# CORESP12.net
KiCad netlist of a schematic drawn in EAGLE
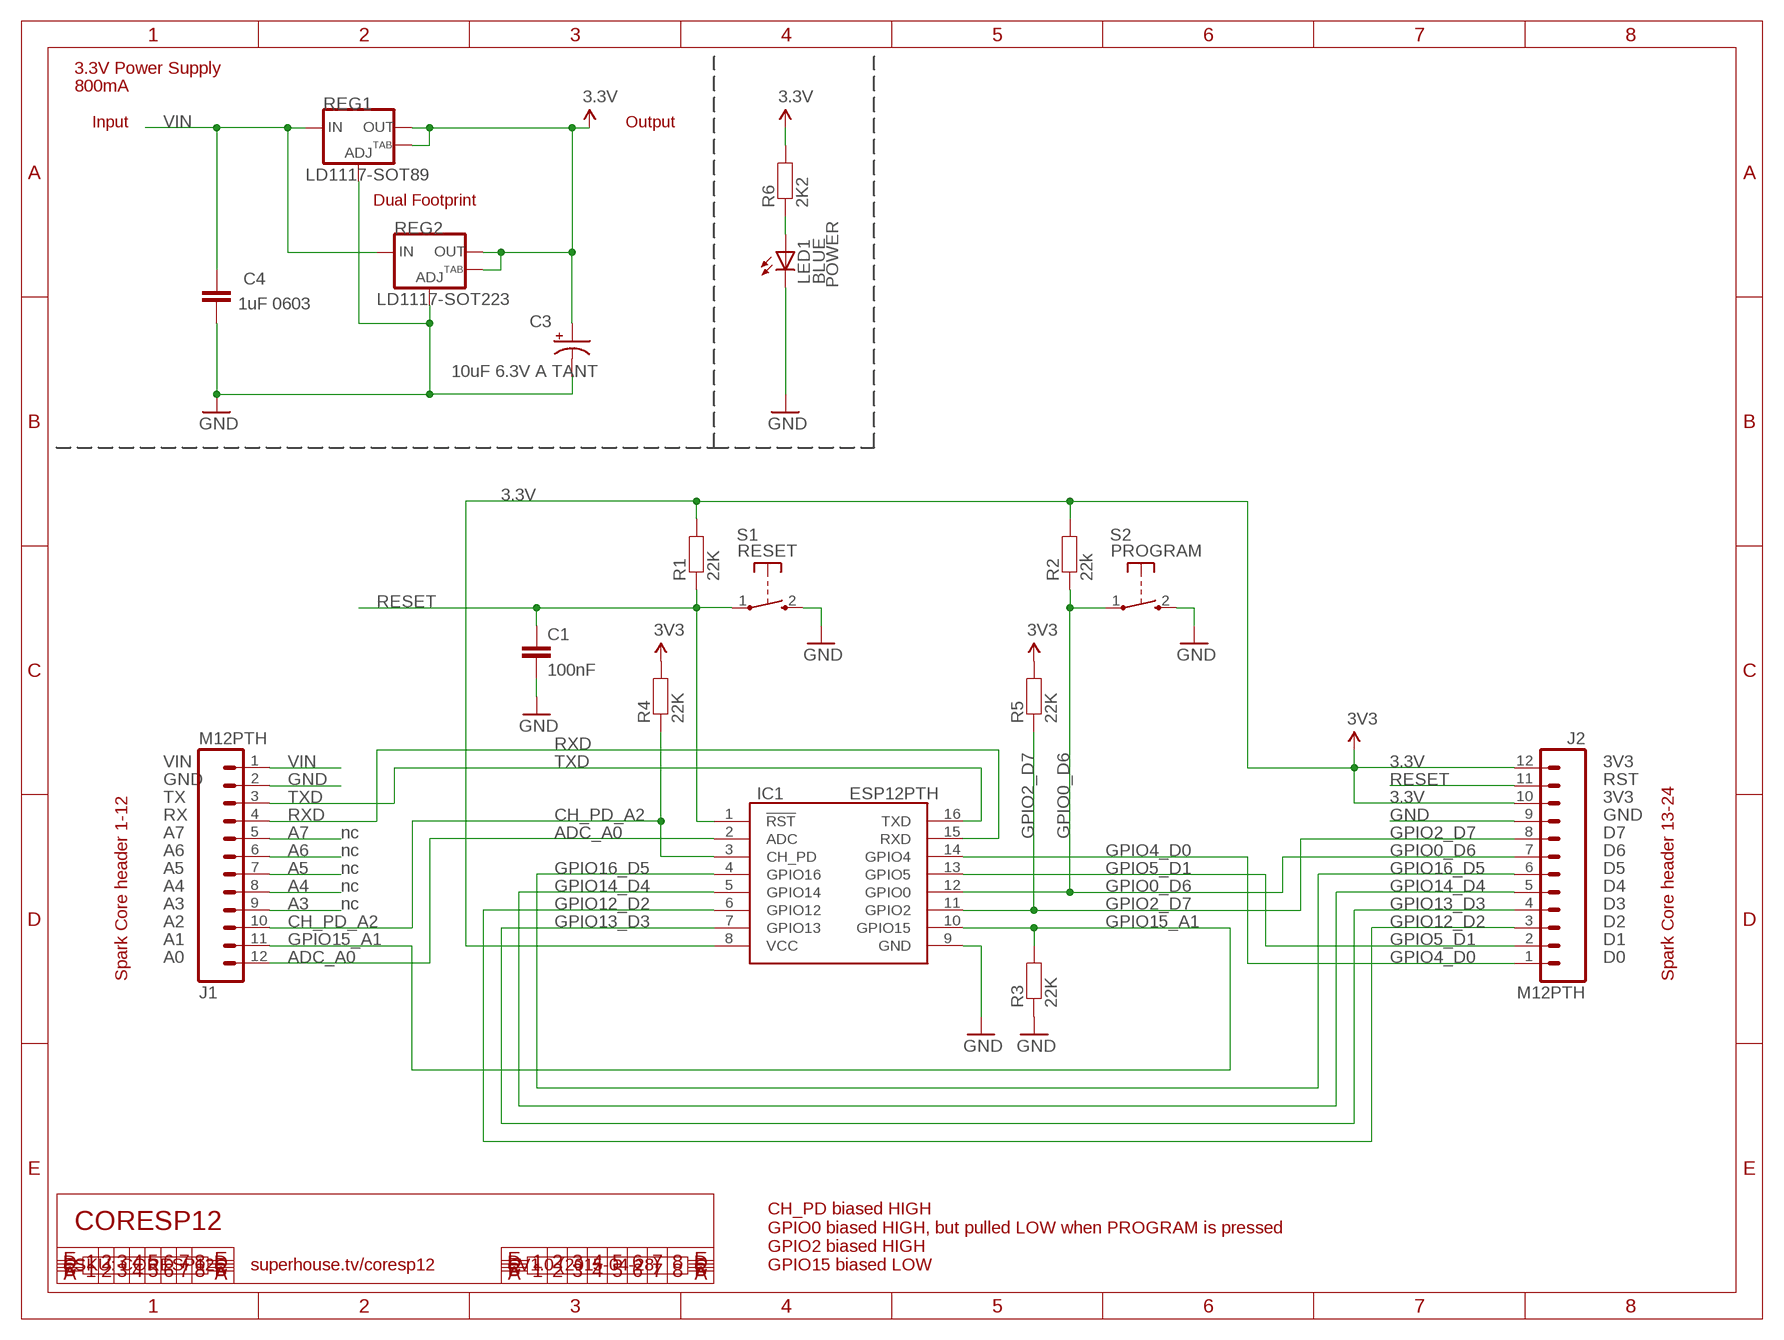
[diagram p0: schematic, sheet 1]

(export (version "E")
  (design (tool "Eeschema 10.0.6"))
  (components
    (comp (ref "C1")
      (value "100nF")
      (footprint "eagle-import:0603")
      (libsource (lib "eagle-import") (part "freetronics-master-v1.1_CAP0603"))
    )
    (comp (ref "C3")
      (value "10uF 6.3V A TANT")
      (footprint "eagle-import:EIA3216")
      (libsource (lib "eagle-import") (part "CAP_POL1206"))
    )
    (comp (ref "C4")
      (value "1uF 0603")
      (footprint "eagle-import:0603")
      (libsource (lib "eagle-import") (part "CAP0603"))
    )
    (comp (ref "IC1")
      (value "ESP12PTH")
      (footprint "eagle-import:ESP12PTH")
      (libsource (lib "eagle-import") (part "ESP12PTH"))
    )
    (comp (ref "J1")
      (value "M12PTH")
      (footprint "eagle-import:1X12")
      (libsource (lib "eagle-import") (part "M12PTH"))
    )
    (comp (ref "J2")
      (value "M12PTH")
      (footprint "eagle-import:1X12")
      (libsource (lib "eagle-import") (part "M12PTH"))
    )
    (comp (ref "LED1")
      (value "BLUE")
      (footprint "eagle-import:LED-0603")
      (libsource (lib "eagle-import") (part "LED0603"))
    )
    (comp (ref "R1")
      (value "22K")
      (footprint "eagle-import:0603")
      (libsource (lib "eagle-import") (part "freetronics-master-v1.1_RESISTOR0603"))
    )
    (comp (ref "R2")
      (value "22k")
      (footprint "eagle-import:0603")
      (libsource (lib "eagle-import") (part "freetronics-master-v1.1_RESISTOR0603"))
    )
    (comp (ref "R3")
      (value "22K")
      (footprint "eagle-import:0603")
      (libsource (lib "eagle-import") (part "freetronics-master-v1.1_RESISTOR0603"))
    )
    (comp (ref "R4")
      (value "22K")
      (footprint "eagle-import:0603")
      (libsource (lib "eagle-import") (part "freetronics-master-v1.1_RESISTOR0603"))
    )
    (comp (ref "R5")
      (value "22K")
      (footprint "eagle-import:0603")
      (libsource (lib "eagle-import") (part "freetronics-master-v1.1_RESISTOR0603"))
    )
    (comp (ref "R6")
      (value "2K2")
      (footprint "eagle-import:0603")
      (libsource (lib "eagle-import") (part "RESISTOR0603"))
    )
    (comp (ref "REG1")
      (value "LD1117-SOT89")
      (footprint "eagle-import:SOT89")
      (libsource (lib "eagle-import") (part "V_REG_LM1117SOT89"))
    )
    (comp (ref "REG2")
      (value "LD1117-SOT223")
      (footprint "eagle-import:SOT223")
      (libsource (lib "eagle-import") (part "V_REG_LM1117SOT223"))
    )
    (comp (ref "S1")
      (value "RESET")
      (footprint "eagle-import:TACTILE_SWITCH_SMD_2PIN_TINY")
      (libsource (lib "eagle-import") (part "TAC_SWITCH_2PIN"))
    )
    (comp (ref "S2")
      (value "PROGRAM")
      (footprint "eagle-import:TACTILE_SWITCH_SMD_2PIN_TINY")
      (libsource (lib "eagle-import") (part "TAC_SWITCH_2PIN"))
    )
  )
  (nets
    (net (code "1") (name "/A3") (class "Default")
      (node (ref "J1") (pin "9") (pinfunction "9_9") (pintype "passive"))
    )
    (net (code "2") (name "/A4") (class "Default")
      (node (ref "J1") (pin "8") (pinfunction "8_8") (pintype "passive"))
    )
    (net (code "3") (name "/A5") (class "Default")
      (node (ref "J1") (pin "7") (pinfunction "7_7") (pintype "passive"))
    )
    (net (code "4") (name "/A6") (class "Default")
      (node (ref "J1") (pin "6") (pinfunction "6_6") (pintype "passive"))
    )
    (net (code "5") (name "/A7") (class "Default")
      (node (ref "J1") (pin "5") (pinfunction "5_5") (pintype "passive"))
    )
    (net (code "6") (name "/ADC_A0") (class "Default")
      (node (ref "IC1") (pin "2") (pinfunction "ADC_2") (pintype "input"))
      (node (ref "J1") (pin "12") (pinfunction "12_12") (pintype "passive"))
    )
    (net (code "7") (name "/CH_PD_A2") (class "Default")
      (node (ref "IC1") (pin "3") (pinfunction "CH_PD_3") (pintype "input"))
      (node (ref "J1") (pin "10") (pinfunction "10_10") (pintype "passive"))
      (node (ref "R4") (pin "1") (pinfunction "1_1") (pintype "passive"))
    )
    (net (code "8") (name "/GPIO0_D6") (class "Default")
      (node (ref "IC1") (pin "12") (pinfunction "GPIO0_12") (pintype "bidirectional"))
      (node (ref "J2") (pin "7") (pinfunction "7_7") (pintype "passive"))
      (node (ref "R2") (pin "1") (pinfunction "1_1") (pintype "passive"))
      (node (ref "S2") (pin "1") (pinfunction "P_1") (pintype "passive"))
    )
    (net (code "9") (name "/GPIO2_D7") (class "Default")
      (node (ref "IC1") (pin "11") (pinfunction "GPIO2_11") (pintype "bidirectional"))
      (node (ref "J2") (pin "8") (pinfunction "8_8") (pintype "passive"))
      (node (ref "R5") (pin "1") (pinfunction "1_1") (pintype "passive"))
    )
    (net (code "10") (name "/GPIO4_D0") (class "Default")
      (node (ref "IC1") (pin "14") (pinfunction "GPIO4_14") (pintype "bidirectional"))
      (node (ref "J2") (pin "1") (pinfunction "1_1") (pintype "passive"))
    )
    (net (code "11") (name "/GPIO5_D1") (class "Default")
      (node (ref "IC1") (pin "13") (pinfunction "GPIO5_13") (pintype "bidirectional"))
      (node (ref "J2") (pin "2") (pinfunction "2_2") (pintype "passive"))
    )
    (net (code "12") (name "/GPIO12_D2") (class "Default")
      (node (ref "IC1") (pin "6") (pinfunction "GPIO12_6") (pintype "bidirectional"))
      (node (ref "J2") (pin "3") (pinfunction "3_3") (pintype "passive"))
    )
    (net (code "13") (name "/GPIO13_D3") (class "Default")
      (node (ref "IC1") (pin "7") (pinfunction "GPIO13_7") (pintype "bidirectional"))
      (node (ref "J2") (pin "4") (pinfunction "4_4") (pintype "passive"))
    )
    (net (code "14") (name "/GPIO14_D4") (class "Default")
      (node (ref "IC1") (pin "5") (pinfunction "GPIO14_5") (pintype "bidirectional"))
      (node (ref "J2") (pin "5") (pinfunction "5_5") (pintype "passive"))
    )
    (net (code "15") (name "/GPIO15_A1") (class "Default")
      (node (ref "IC1") (pin "10") (pinfunction "GPIO15_10") (pintype "bidirectional"))
      (node (ref "J1") (pin "11") (pinfunction "11_11") (pintype "passive"))
      (node (ref "R3") (pin "2") (pinfunction "2_2") (pintype "passive"))
    )
    (net (code "16") (name "/GPIO16_D5") (class "Default")
      (node (ref "IC1") (pin "4") (pinfunction "GPIO16_4") (pintype "bidirectional"))
      (node (ref "J2") (pin "6") (pinfunction "6_6") (pintype "passive"))
    )
    (net (code "17") (name "/RESET") (class "Default")
      (node (ref "C1") (pin "1") (pinfunction "1_1") (pintype "passive"))
      (node (ref "IC1") (pin "1") (pinfunction "~{RST}_1") (pintype "bidirectional"))
      (node (ref "J2") (pin "11") (pinfunction "11_11") (pintype "passive"))
      (node (ref "R1") (pin "1") (pinfunction "1_1") (pintype "passive"))
      (node (ref "S1") (pin "1") (pinfunction "P_1") (pintype "passive"))
    )
    (net (code "18") (name "/RXD") (class "Default")
      (node (ref "IC1") (pin "15") (pinfunction "RXD_15") (pintype "input"))
      (node (ref "J1") (pin "4") (pinfunction "4_4") (pintype "passive"))
    )
    (net (code "19") (name "/TXD") (class "Default")
      (node (ref "IC1") (pin "16") (pinfunction "TXD_16") (pintype "output"))
      (node (ref "J1") (pin "3") (pinfunction "3_3") (pintype "passive"))
    )
    (net (code "20") (name "/VIN") (class "Default")
      (node (ref "C4") (pin "1") (pinfunction "1_1") (pintype "passive"))
      (node (ref "J1") (pin "1") (pinfunction "1_1") (pintype "passive"))
      (node (ref "REG1") (pin "3") (pinfunction "IN_3") (pintype "input"))
      (node (ref "REG2") (pin "3") (pinfunction "IN_3") (pintype "input"))
    )
    (net (code "21") (name "3.3V") (class "Default")
      (node (ref "C3") (pin "A") (pinfunction "+_A") (pintype "passive"))
      (node (ref "IC1") (pin "8") (pinfunction "VCC_8") (pintype "power_in"))
      (node (ref "J2") (pin "10") (pinfunction "10_10") (pintype "passive"))
      (node (ref "J2") (pin "12") (pinfunction "12_12") (pintype "passive"))
      (node (ref "R1") (pin "2") (pinfunction "2_2") (pintype "passive"))
      (node (ref "R2") (pin "2") (pinfunction "2_2") (pintype "passive"))
      (node (ref "R4") (pin "2") (pinfunction "2_2") (pintype "passive"))
      (node (ref "R5") (pin "2") (pinfunction "2_2") (pintype "passive"))
      (node (ref "R6") (pin "2") (pinfunction "2_2") (pintype "passive"))
      (node (ref "REG1") (pin "2") (pinfunction "OUT_2") (pintype "output"))
      (node (ref "REG1") (pin "4") (pinfunction "OUT_4") (pintype "output"))
      (node (ref "REG2") (pin "2") (pinfunction "OUT_2") (pintype "output"))
      (node (ref "REG2") (pin "4") (pinfunction "OUT_4") (pintype "output"))
    )
    (net (code "22") (name "GND") (class "Default")
      (node (ref "C1") (pin "2") (pinfunction "2_2") (pintype "passive"))
      (node (ref "C3") (pin "C") (pinfunction "-_C") (pintype "passive"))
      (node (ref "C4") (pin "2") (pinfunction "2_2") (pintype "passive"))
      (node (ref "IC1") (pin "9") (pinfunction "GND_9") (pintype "power_in"))
      (node (ref "J1") (pin "2") (pinfunction "2_2") (pintype "passive"))
      (node (ref "J2") (pin "9") (pinfunction "9_9") (pintype "passive"))
      (node (ref "LED1") (pin "C") (pinfunction "C_C") (pintype "passive"))
      (node (ref "R3") (pin "1") (pinfunction "1_1") (pintype "passive"))
      (node (ref "REG1") (pin "1") (pinfunction "ADJ_1") (pintype "input"))
      (node (ref "REG2") (pin "1") (pinfunction "ADJ_1") (pintype "input"))
      (node (ref "S1") (pin "2") (pinfunction "S_2") (pintype "passive"))
      (node (ref "S2") (pin "2") (pinfunction "S_2") (pintype "passive"))
    )
    (net (code "23") (name "Net-(LED1-PadA)") (class "Default")
      (node (ref "LED1") (pin "A") (pinfunction "A_A") (pintype "passive"))
      (node (ref "R6") (pin "1") (pinfunction "1_1") (pintype "passive"))
    )
  )
)
